# MyPCB_Homework.net
KiCad netlist of a schematic drawn in Altium Designer
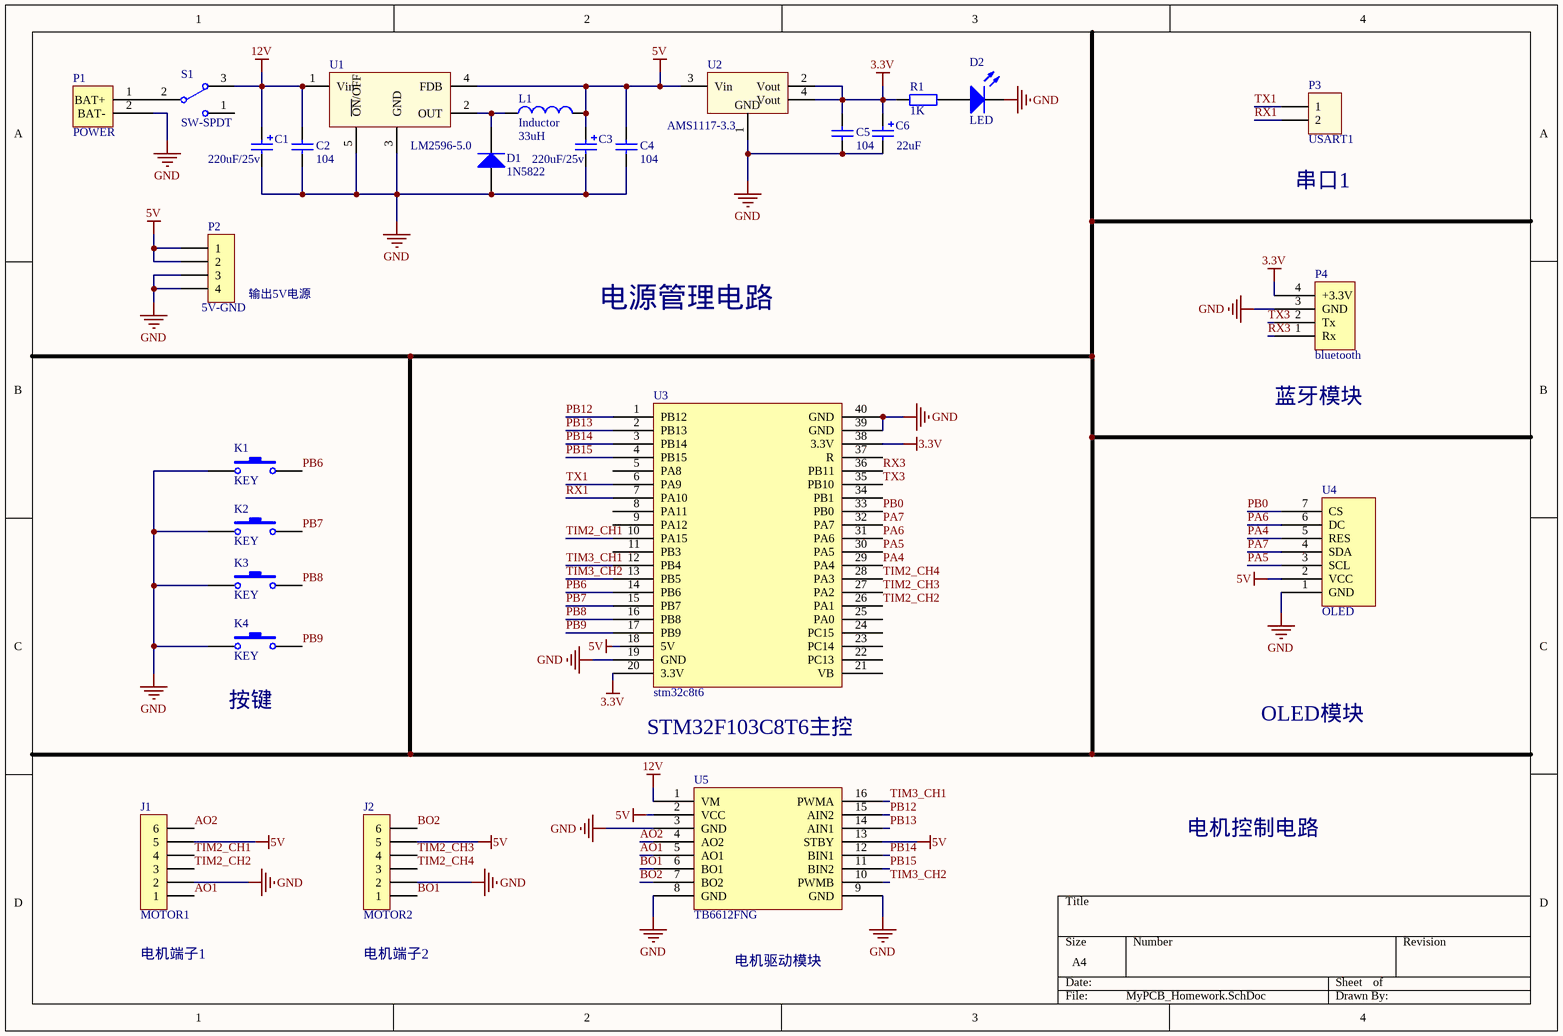
[diagram p0: MyPCB_Homework.SchDoc]

(export (version "E")
  (design (tool "Eeschema 10.0.6"))
  (components
    (comp (ref "C1")
      (value "Cap Pol(22uF)")
      (footprint "CAP POL [25V]")
      (fields (field (name "ALTIUM_UNNAMED_1") "220uF/25v"))
      (libsource (lib "MyPCB_Homework") (part "Cap Pol(22uF)"))
    )
    (comp (ref "C2")
      (value "Cap")
      (footprint "0805C")
      (fields (field (name "ALTIUM_UNNAMED_1") "104"))
      (libsource (lib "MyPCB_Homework") (part "Cap_1"))
    )
    (comp (ref "C3")
      (value "Cap Pol(22uF)")
      (footprint "CAP POL [25V]")
      (fields (field (name "ALTIUM_UNNAMED_1") "220uF/25v"))
      (libsource (lib "MyPCB_Homework") (part "Cap Pol(22uF)"))
    )
    (comp (ref "C4")
      (value "Cap")
      (footprint "0805C")
      (fields (field (name "ALTIUM_UNNAMED_1") "104"))
      (libsource (lib "MyPCB_Homework") (part "Cap_1"))
    )
    (comp (ref "C5")
      (value "Cap")
      (footprint "0805C")
      (fields (field (name "ALTIUM_UNNAMED_1") "104"))
      (libsource (lib "MyPCB_Homework") (part "Cap_1"))
    )
    (comp (ref "C6")
      (value "Cap Pol(22uF)")
      (footprint "CAP[1210]")
      (fields (field (name "ALTIUM_UNNAMED_1") "22uF"))
      (libsource (lib "MyPCB_Homework") (part "Cap Pol(22uF)"))
    )
    (comp (ref "D1")
      (value "1N5822")
      (footprint "0805LED1")
      (libsource (lib "MyPCB_Homework") (part "1N5819"))
    )
    (comp (ref "D2")
      (value "LED")
      (footprint "0805LED1")
      (description "LED_BLUE")
      (libsource (lib "MyPCB_Homework") (part "LED_BLUE"))
    )
    (comp (ref "J1")
      (value "MOTOR1")
      (footprint "XH2.54-LI-6P")
      (description "Connector")
      (libsource (lib "MyPCB_Homework") (part "XH-2.54-6"))
    )
    (comp (ref "J2")
      (value "MOTOR2")
      (footprint "XH2.54-LI-6P")
      (description "Connector")
      (libsource (lib "MyPCB_Homework") (part "XH-2.54-6"))
    )
    (comp (ref "K1") (value "KEY") (footprint "KEl") (libsource (lib "MyPCB_Homework") (part "KEY")))
    (comp (ref "K2") (value "KEY") (footprint "KEl") (libsource (lib "MyPCB_Homework") (part "KEY")))
    (comp (ref "K3") (value "KEY") (footprint "KEl") (libsource (lib "MyPCB_Homework") (part "KEY")))
    (comp (ref "K4") (value "KEY") (footprint "KEl") (libsource (lib "MyPCB_Homework") (part "KEY")))
    (comp (ref "L1")
      (value "Inductor")
      (footprint "Inductor_T10uH")
      (fields (field (name "ALTIUM_UNNAMED_1") "33uH"))
      (libsource (lib "MyPCB_Homework") (part "Inductor_1"))
    )
    (comp (ref "P1") (value "POWER") (footprint "电源端子") (libsource (lib "MyPCB_Homework") (part "power")))
    (comp (ref "P2")
      (value "5V-GND")
      (footprint "4p-接线端子")
      (description "Connector")
      (libsource (lib "MyPCB_Homework") (part "CON4"))
    )
    (comp (ref "P3")
      (value "USART1")
      (footprint "HDR1X2")
      (description "H2X1")
      (libsource (lib "MyPCB_Homework") (part "H2X1"))
    )
    (comp (ref "P4")
      (value "bluetooth")
      (footprint "bluetooth")
      (libsource (lib "MyPCB_Homework") (part "Bluetooth"))
    )
    (comp (ref "R1")
      (value "1K")
      (footprint "0805R")
      (description "Resistor")
      (fields (field (name "PUBLISHER") "Altium Limited"))
      (libsource (lib "Miscellaneous Devices") (part "Res2"))
    )
    (comp (ref "S1")
      (value "SW-SPDT")
      (footprint "SW-TO3")
      (description "SPDT Subminiature Toggle Switch, Right Angle Mounting, Vertical Actuation")
      (fields (field (name "PUBLISHER") "Altium Limited"))
      (libsource (lib "MyPCB_Homework") (part "SW-SPDT"))
    )
    (comp (ref "U1")
      (value "LM2596-5.0")
      (footprint "TO-263-5")
      (description "IC")
      (libsource (lib "MyPCB_Homework") (part "LM2596-5.0"))
    )
    (comp (ref "U2")
      (value "AMS1117-3.3")
      (footprint "SOT-223")
      (libsource (lib "MyPCB_Homework") (part "AMS1117-3.3"))
    )
    (comp (ref "U3")
      (value "stm32c8t6")
      (footprint "STM32F103C8T6最小系统1")
      (libsource (lib "MyPCB_Homework") (part "stm32c8t6"))
    )
    (comp (ref "U4") (value "OLED") (footprint "OLED") (libsource (lib "MyPCB_Homework") (part "oled")))
    (comp (ref "U5")
      (value "TB6612FNG")
      (footprint "TB6612FNG")
      (libsource (lib "MyPCB_Homework") (part "TB6612"))
    )
  )
  (nets
    (net (code "1") (name "/AO1") (class "Default")
      (node (ref "J1") (pin "1") (pinfunction "1_1") (pintype "passive"))
      (node (ref "U5") (pin "5") (pinfunction "AO1_5") (pintype "passive"))
    )
    (net (code "2") (name "/AO2") (class "Default")
      (node (ref "J1") (pin "6") (pinfunction "6_6") (pintype "passive"))
      (node (ref "U5") (pin "4") (pinfunction "AO2_4") (pintype "passive"))
    )
    (net (code "3") (name "/BO1") (class "Default")
      (node (ref "J2") (pin "1") (pinfunction "1_1") (pintype "passive"))
      (node (ref "U5") (pin "6") (pinfunction "BO1_6") (pintype "passive"))
    )
    (net (code "4") (name "/BO2") (class "Default")
      (node (ref "J2") (pin "6") (pinfunction "6_6") (pintype "passive"))
      (node (ref "U5") (pin "7") (pinfunction "BO2_7") (pintype "passive"))
    )
    (net (code "5") (name "/PA4") (class "Default")
      (node (ref "U3") (pin "29") (pinfunction "PA4_29") (pintype "passive"))
      (node (ref "U4") (pin "5") (pinfunction "RES_5") (pintype "passive"))
    )
    (net (code "6") (name "/PA5") (class "Default")
      (node (ref "U3") (pin "30") (pinfunction "PA5_30") (pintype "passive"))
      (node (ref "U4") (pin "3") (pinfunction "SCL_3") (pintype "passive"))
    )
    (net (code "7") (name "/PA6") (class "Default")
      (node (ref "U3") (pin "31") (pinfunction "PA6_31") (pintype "passive"))
      (node (ref "U4") (pin "6") (pinfunction "DC_6") (pintype "passive"))
    )
    (net (code "8") (name "/PA7") (class "Default")
      (node (ref "U3") (pin "32") (pinfunction "PA7_32") (pintype "passive"))
      (node (ref "U4") (pin "4") (pinfunction "SDA_4") (pintype "passive"))
    )
    (net (code "9") (name "/PB0") (class "Default")
      (node (ref "U3") (pin "33") (pinfunction "PB0_33") (pintype "passive"))
      (node (ref "U4") (pin "7") (pinfunction "CS_7") (pintype "passive"))
    )
    (net (code "10") (name "/PB6") (class "Default")
      (node (ref "K1") (pin "2") (pinfunction "2_2") (pintype "passive"))
      (node (ref "U3") (pin "14") (pinfunction "PB6_14") (pintype "passive"))
    )
    (net (code "11") (name "/PB7") (class "Default")
      (node (ref "K2") (pin "2") (pinfunction "2_2") (pintype "passive"))
      (node (ref "U3") (pin "15") (pinfunction "PB7_15") (pintype "passive"))
    )
    (net (code "12") (name "/PB8") (class "Default")
      (node (ref "K3") (pin "2") (pinfunction "2_2") (pintype "passive"))
      (node (ref "U3") (pin "16") (pinfunction "PB8_16") (pintype "passive"))
    )
    (net (code "13") (name "/PB9") (class "Default")
      (node (ref "K4") (pin "2") (pinfunction "2_2") (pintype "passive"))
      (node (ref "U3") (pin "17") (pinfunction "PB9_17") (pintype "passive"))
    )
    (net (code "14") (name "/PB12") (class "Default")
      (node (ref "U3") (pin "1") (pinfunction "PB12_1") (pintype "passive"))
      (node (ref "U5") (pin "15") (pinfunction "AIN2_15") (pintype "passive"))
    )
    (net (code "15") (name "/PB13") (class "Default")
      (node (ref "U3") (pin "2") (pinfunction "PB13_2") (pintype "passive"))
      (node (ref "U5") (pin "14") (pinfunction "AIN1_14") (pintype "passive"))
    )
    (net (code "16") (name "/PB14") (class "Default")
      (node (ref "U3") (pin "3") (pinfunction "PB14_3") (pintype "passive"))
      (node (ref "U5") (pin "12") (pinfunction "BIN1_12") (pintype "passive"))
    )
    (net (code "17") (name "/PB15") (class "Default")
      (node (ref "U3") (pin "4") (pinfunction "PB15_4") (pintype "passive"))
      (node (ref "U5") (pin "11") (pinfunction "BIN2_11") (pintype "passive"))
    )
    (net (code "18") (name "/RX1") (class "Default")
      (node (ref "P3") (pin "2") (pinfunction "2_2") (pintype "passive"))
      (node (ref "U3") (pin "7") (pinfunction "PA10_7") (pintype "passive"))
    )
    (net (code "19") (name "/RX3") (class "Default")
      (node (ref "P4") (pin "1") (pinfunction "Rx_1") (pintype "passive"))
      (node (ref "U3") (pin "36") (pinfunction "PB11_36") (pintype "passive"))
    )
    (net (code "20") (name "/TIM2_CH1") (class "Default")
      (node (ref "J1") (pin "4") (pinfunction "4_4") (pintype "passive"))
      (node (ref "U3") (pin "10") (pinfunction "PA15_10") (pintype "passive"))
    )
    (net (code "21") (name "/TIM2_CH2") (class "Default")
      (node (ref "J1") (pin "3") (pinfunction "3_3") (pintype "passive"))
      (node (ref "U3") (pin "26") (pinfunction "PA1_26") (pintype "passive"))
    )
    (net (code "22") (name "/TIM2_CH3") (class "Default")
      (node (ref "J2") (pin "4") (pinfunction "4_4") (pintype "passive"))
      (node (ref "U3") (pin "27") (pinfunction "PA2_27") (pintype "passive"))
    )
    (net (code "23") (name "/TIM2_CH4") (class "Default")
      (node (ref "J2") (pin "3") (pinfunction "3_3") (pintype "passive"))
      (node (ref "U3") (pin "28") (pinfunction "PA3_28") (pintype "passive"))
    )
    (net (code "24") (name "/TIM3_CH1") (class "Default")
      (node (ref "U3") (pin "12") (pinfunction "PB4_12") (pintype "passive"))
      (node (ref "U5") (pin "16") (pinfunction "PWMA_16") (pintype "passive"))
    )
    (net (code "25") (name "/TIM3_CH2") (class "Default")
      (node (ref "U3") (pin "13") (pinfunction "PB5_13") (pintype "passive"))
      (node (ref "U5") (pin "10") (pinfunction "PWMB_10") (pintype "passive"))
    )
    (net (code "26") (name "/TX1") (class "Default")
      (node (ref "P3") (pin "1") (pinfunction "1_1") (pintype "passive"))
      (node (ref "U3") (pin "6") (pinfunction "PA9_6") (pintype "passive"))
    )
    (net (code "27") (name "/TX3") (class "Default")
      (node (ref "P4") (pin "2") (pinfunction "Tx_2") (pintype "passive"))
      (node (ref "U3") (pin "35") (pinfunction "PB10_35") (pintype "passive"))
    )
    (net (code "28") (name "3.3V") (class "Default")
      (node (ref "C5") (pin "2") (pinfunction "2_2") (pintype "passive"))
      (node (ref "C6") (pin "1") (pinfunction "1_1") (pintype "passive"))
      (node (ref "P4") (pin "4") (pinfunction "+3.3V_4") (pintype "passive"))
      (node (ref "R1") (pin "1") (pinfunction "1_1") (pintype "passive"))
      (node (ref "U2") (pin "2") (pinfunction "Vout_2") (pintype "passive"))
      (node (ref "U2") (pin "4") (pinfunction "Vout_4") (pintype "passive"))
      (node (ref "U3") (pin "20") (pinfunction "3.3V_20") (pintype "passive"))
      (node (ref "U3") (pin "38") (pinfunction "3.3V_38") (pintype "passive"))
    )
    (net (code "29") (name "5V") (class "Default")
      (node (ref "C3") (pin "1") (pinfunction "1_1") (pintype "passive"))
      (node (ref "C4") (pin "2") (pinfunction "2_2") (pintype "passive"))
      (node (ref "J1") (pin "5") (pinfunction "5_5") (pintype "passive"))
      (node (ref "J2") (pin "5") (pinfunction "5_5") (pintype "passive"))
      (node (ref "L1") (pin "2") (pinfunction "2_2") (pintype "passive"))
      (node (ref "P2") (pin "1") (pinfunction "1_1") (pintype "passive"))
      (node (ref "P2") (pin "2") (pinfunction "2_2") (pintype "passive"))
      (node (ref "U1") (pin "4") (pinfunction "FDB_4") (pintype "passive"))
      (node (ref "U2") (pin "3") (pinfunction "Vin_3") (pintype "passive"))
      (node (ref "U3") (pin "18") (pinfunction "5V_18") (pintype "passive"))
      (node (ref "U4") (pin "2") (pinfunction "VCC_2") (pintype "passive"))
      (node (ref "U5") (pin "13") (pinfunction "STBY_13") (pintype "passive"))
      (node (ref "U5") (pin "2") (pinfunction "VCC_2") (pintype "passive"))
    )
    (net (code "30") (name "12V") (class "Default")
      (node (ref "C1") (pin "1") (pinfunction "1_1") (pintype "passive"))
      (node (ref "C2") (pin "2") (pinfunction "2_2") (pintype "passive"))
      (node (ref "S1") (pin "3") (pinfunction "3_3") (pintype "passive"))
      (node (ref "U1") (pin "1") (pinfunction "Vin_1") (pintype "passive"))
      (node (ref "U5") (pin "1") (pinfunction "VM_1") (pintype "passive"))
    )
    (net (code "31") (name "GND") (class "Default")
      (node (ref "C1") (pin "2") (pinfunction "2_2") (pintype "passive"))
      (node (ref "C2") (pin "1") (pinfunction "1_1") (pintype "passive"))
      (node (ref "C3") (pin "2") (pinfunction "2_2") (pintype "passive"))
      (node (ref "C4") (pin "1") (pinfunction "1_1") (pintype "passive"))
      (node (ref "C5") (pin "1") (pinfunction "1_1") (pintype "passive"))
      (node (ref "C6") (pin "2") (pinfunction "2_2") (pintype "passive"))
      (node (ref "D1") (pin "1") (pinfunction "1_1") (pintype "passive"))
      (node (ref "D2") (pin "2") (pinfunction "K_2") (pintype "passive"))
      (node (ref "J1") (pin "2") (pinfunction "2_2") (pintype "passive"))
      (node (ref "J2") (pin "2") (pinfunction "2_2") (pintype "passive"))
      (node (ref "K1") (pin "1") (pinfunction "1_1") (pintype "passive"))
      (node (ref "K2") (pin "1") (pinfunction "1_1") (pintype "passive"))
      (node (ref "K3") (pin "1") (pinfunction "1_1") (pintype "passive"))
      (node (ref "K4") (pin "1") (pinfunction "1_1") (pintype "passive"))
      (node (ref "P1") (pin "2") (pinfunction "BAT-_2") (pintype "passive"))
      (node (ref "P2") (pin "3") (pinfunction "3_3") (pintype "passive"))
      (node (ref "P2") (pin "4") (pinfunction "4_4") (pintype "passive"))
      (node (ref "P4") (pin "3") (pinfunction "GND_3") (pintype "passive"))
      (node (ref "U1") (pin "3") (pinfunction "GND_3") (pintype "passive"))
      (node (ref "U1") (pin "5") (pinfunction "~{ON}/OFF_5") (pintype "passive"))
      (node (ref "U2") (pin "1") (pinfunction "GND_1") (pintype "passive"))
      (node (ref "U3") (pin "19") (pinfunction "GND_19") (pintype "passive"))
      (node (ref "U3") (pin "39") (pinfunction "GND_39") (pintype "passive"))
      (node (ref "U3") (pin "40") (pinfunction "GND_40") (pintype "passive"))
      (node (ref "U4") (pin "1") (pinfunction "GND_1") (pintype "passive"))
      (node (ref "U5") (pin "3") (pinfunction "GND_3") (pintype "passive"))
      (node (ref "U5") (pin "8") (pinfunction "GND_8") (pintype "passive"))
      (node (ref "U5") (pin "9") (pinfunction "GND_9") (pintype "passive"))
    )
    (net (code "32") (name "Net-(D2-A)") (class "Default")
      (node (ref "D2") (pin "1") (pinfunction "A_1") (pintype "passive"))
      (node (ref "R1") (pin "2") (pinfunction "2_2") (pintype "passive"))
    )
    (net (code "33") (name "Net-(P1-BAT+)") (class "Default")
      (node (ref "P1") (pin "1") (pinfunction "BAT+_1") (pintype "passive"))
      (node (ref "S1") (pin "2") (pinfunction "2_2") (pintype "passive"))
    )
    (net (code "34") (name "Net-(U1-OUT)") (class "Default")
      (node (ref "D1") (pin "2") (pinfunction "2_2") (pintype "passive"))
      (node (ref "L1") (pin "1") (pinfunction "1_1") (pintype "passive"))
      (node (ref "U1") (pin "2") (pinfunction "OUT_2") (pintype "passive"))
    )
    (net (code "35") (name "unconnected-(S1-Pad1)") (class "Default")
      (node (ref "S1") (pin "1") (pinfunction "1_1") (pintype "passive"))
    )
    (net (code "36") (name "unconnected-(U3-PA0-Pad25)") (class "Default")
      (node (ref "U3") (pin "25") (pinfunction "PA0_25") (pintype "passive"))
    )
    (net (code "37") (name "unconnected-(U3-PA8-Pad5)") (class "Default")
      (node (ref "U3") (pin "5") (pinfunction "PA8_5") (pintype "passive"))
    )
    (net (code "38") (name "unconnected-(U3-PA11-Pad8)") (class "Default")
      (node (ref "U3") (pin "8") (pinfunction "PA11_8") (pintype "passive"))
    )
    (net (code "39") (name "unconnected-(U3-PA12-Pad9)") (class "Default")
      (node (ref "U3") (pin "9") (pinfunction "PA12_9") (pintype "passive"))
    )
    (net (code "40") (name "unconnected-(U3-PB1-Pad34)") (class "Default")
      (node (ref "U3") (pin "34") (pinfunction "PB1_34") (pintype "passive"))
    )
    (net (code "41") (name "unconnected-(U3-PB3-Pad11)") (class "Default")
      (node (ref "U3") (pin "11") (pinfunction "PB3_11") (pintype "passive"))
    )
    (net (code "42") (name "unconnected-(U3-PC13-Pad22)") (class "Default")
      (node (ref "U3") (pin "22") (pinfunction "PC13_22") (pintype "passive"))
    )
    (net (code "43") (name "unconnected-(U3-PC14-Pad23)") (class "Default")
      (node (ref "U3") (pin "23") (pinfunction "PC14_23") (pintype "passive"))
    )
    (net (code "44") (name "unconnected-(U3-PC15-Pad24)") (class "Default")
      (node (ref "U3") (pin "24") (pinfunction "PC15_24") (pintype "passive"))
    )
    (net (code "45") (name "unconnected-(U3-R-Pad37)") (class "Default")
      (node (ref "U3") (pin "37") (pinfunction "R_37") (pintype "passive"))
    )
    (net (code "46") (name "unconnected-(U3-VB-Pad21)") (class "Default")
      (node (ref "U3") (pin "21") (pinfunction "VB_21") (pintype "passive"))
    )
  )
)
